# RELAY.net
KiCad netlist of a schematic drawn in Altium Designer
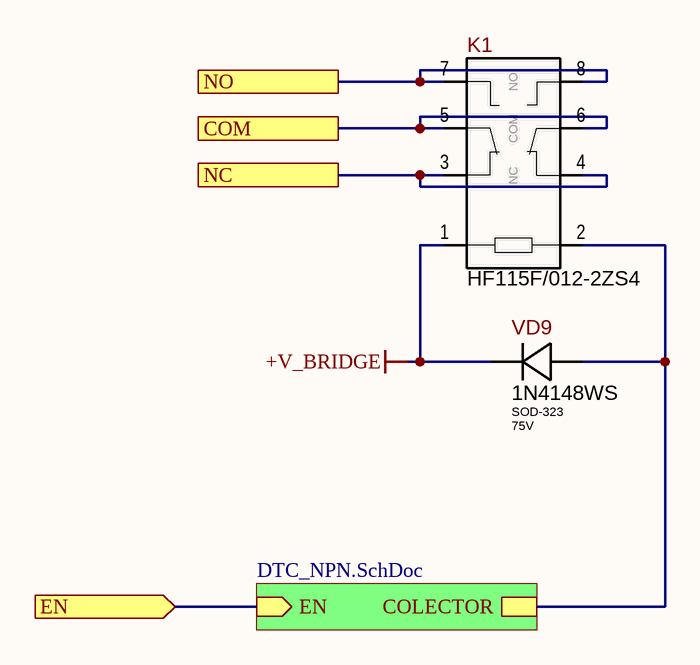
[diagram p0: RELAY.SchDoc]

(export (version "E")
  (design (tool "Eeschema 10.0.6"))
  (components
    (comp (ref "K1")
      (value "HF115F/012-2ZS4")
      (footprint "HF115Fxxx-1(2)Zx3(4)")
      (description "Miniature High Power Relay, DPDT (2 Form C), 12VDC 400mW Coil, 5.0mm 2 Pole 8A AgCdO")
      (fields (field (name "PART NUMBER") "HF115F/012-2ZS4") (field (name "MANUFACTURER") "Hongfa"))
      (libsource (lib "electromechanicals") (part "HF115F/012-2ZS4"))
    )
    (comp (ref "VD9")
      (value "1N4148WS")
      (footprint "SOD-323_MED")
      (description "Diode Standard 75V 150mA, SOD-323F")
      (fields
        (field (name "MANUFACTURER") "Diodec Semiconductor")
        (field (name "PART NUMBER") "1N4148WS")
        (field (name "PACKAGE") "SOD-323")
        (field (name "VOLTAGE") "75V")
      )
      (libsource (lib "diodes") (part "1N4148WS"))
    )
  )
  (nets
    (net (code "1") (name "+V_BRIDGE") (class "Default")
      (node (ref "K1") (pin "1") (pinfunction "COIL1_1") (pintype "passive"))
      (node (ref "VD9") (pin "CA") (pintype "passive"))
    )
    (net (code "2") (name "/COLECTOR") (class "Default")
      (node (ref "K1") (pin "2") (pinfunction "COIL2_2") (pintype "passive"))
      (node (ref "VD9") (pin "AN") (pintype "passive"))
    )
    (net (code "3") (name "/COM") (class "Default")
      (node (ref "K1") (pin "5") (pinfunction "1-COM_5") (pintype "passive"))
      (node (ref "K1") (pin "6") (pinfunction "2-COM_6") (pintype "passive"))
    )
    (net (code "5") (name "/NC") (class "Default")
      (node (ref "K1") (pin "3") (pinfunction "1-NC_3") (pintype "passive"))
      (node (ref "K1") (pin "4") (pinfunction "2-NC_4") (pintype "passive"))
    )
    (net (code "6") (name "/NO") (class "Default")
      (node (ref "K1") (pin "7") (pinfunction "2-NO_7") (pintype "passive"))
      (node (ref "K1") (pin "8") (pinfunction "2-NO_8") (pintype "passive"))
    )
  )
)
